# SCH_-_USB_Passthrough_v2_0.net
KiCad netlist of a schematic drawn in EasyEDA
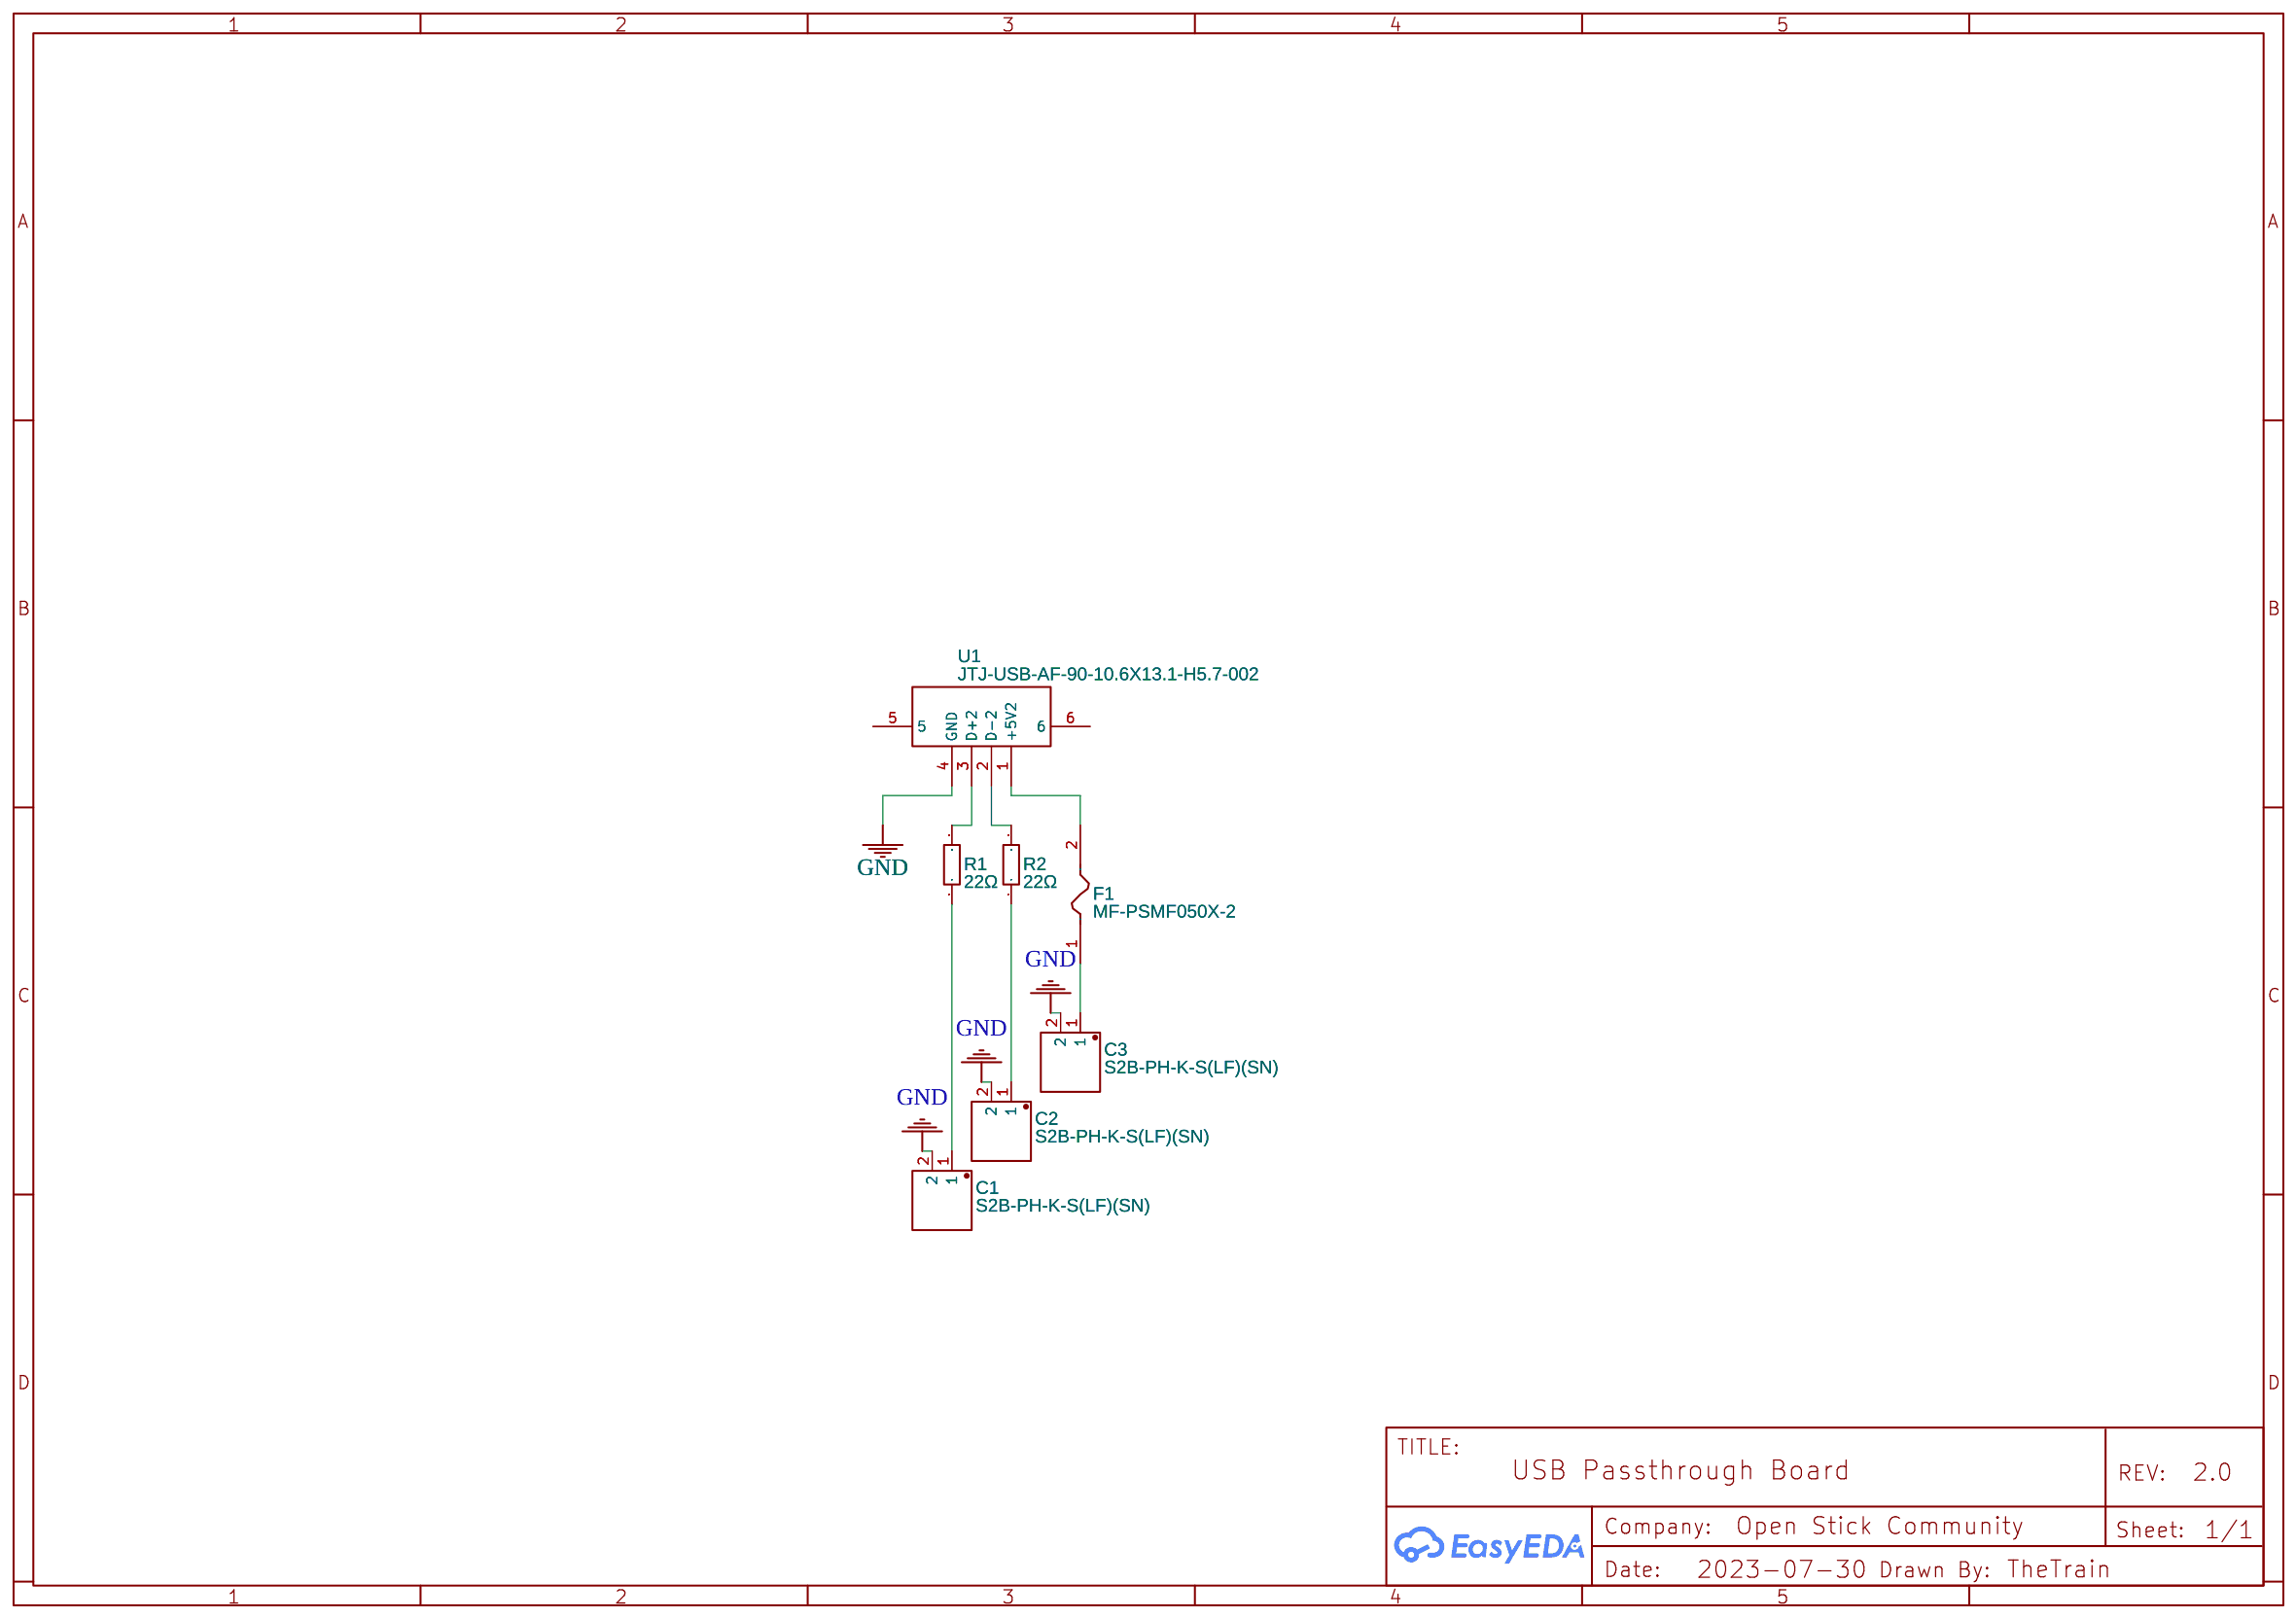
[diagram p0: schematic sheet]

(export (version "E")
  (design (tool "Eeschema 10.0.6"))
  (components
    (comp (ref "C1")
      (value "S2B-PH-K-S(LF)(SN)")
      (fields (field (name "Manufacturer") "JST"))
      (libsource (lib "") (part "S2B-PH-K-S(LF)(SN)"))
    )
    (comp (ref "C2")
      (value "S2B-PH-K-S(LF)(SN)")
      (fields (field (name "Manufacturer") "JST"))
      (libsource (lib "") (part "S2B-PH-K-S(LF)(SN)"))
    )
    (comp (ref "C3")
      (value "S2B-PH-K-S(LF)(SN)")
      (fields (field (name "Manufacturer") "JST"))
      (libsource (lib "") (part "S2B-PH-K-S(LF)(SN)"))
    )
    (comp (ref "F1")
      (value "MF-PSMF050X-2")
      (fields (field (name "Manufacturer") "BOURNS"))
      (libsource (lib "") (part "MF-PSMF050X-2"))
    )
    (comp (ref "R1")
      (value "22Ω")
      (fields
        (field (name "Manufacturer Part") "0603WAF220JT5E")
        (field (name "Manufacturer") "UNI-ROYAL(厚声)")
      )
      (libsource (lib "") (part "0603WAF220JT5E"))
    )
    (comp (ref "R2")
      (value "22Ω")
      (fields
        (field (name "Manufacturer Part") "0603WAF220JT5E")
        (field (name "Manufacturer") "UNI-ROYAL(厚声)")
      )
      (libsource (lib "") (part "0603WAF220JT5E"))
    )
    (comp (ref "U1")
      (value "JTJ-USB-AF-90-10.6X13.1-H5.7-002")
      (fields (field (name "Manufacturer Part") "912-121A2026S10100") (field (name "Manufacturer") "精拓金"))
      (libsource (lib "") (part "JTJ-USB-AF-90-10.6X13.1-H5.7-002"))
    )
  )
  (nets
    (net (code "1") (name "GND") (class "Default")
      (node (ref "C1") (pin "2") (pinfunction "2_2") (pintype "unspecified"))
      (node (ref "C2") (pin "2") (pinfunction "2_2") (pintype "unspecified"))
      (node (ref "C3") (pin "2") (pinfunction "2_2") (pintype "unspecified"))
      (node (ref "U1") (pin "4") (pinfunction "GND_4") (pintype "unspecified"))
    )
    (net (code "2") (name "Net-(C1-Pad1)") (class "Default")
      (node (ref "C1") (pin "1") (pinfunction "1_1") (pintype "unspecified"))
      (node (ref "R1") (pin "1") (pinfunction "1_1") (pintype "input"))
    )
    (net (code "3") (name "Net-(C2-Pad1)") (class "Default")
      (node (ref "C2") (pin "1") (pinfunction "1_1") (pintype "unspecified"))
      (node (ref "R2") (pin "1") (pinfunction "1_1") (pintype "input"))
    )
    (net (code "4") (name "Net-(C3-Pad1)") (class "Default")
      (node (ref "C3") (pin "1") (pinfunction "1_1") (pintype "unspecified"))
      (node (ref "F1") (pin "1") (pinfunction "1_1") (pintype "unspecified"))
    )
    (net (code "5") (name "Net-(U1-+5V2)") (class "Default")
      (node (ref "F1") (pin "2") (pinfunction "2_2") (pintype "unspecified"))
      (node (ref "U1") (pin "1") (pinfunction "+5V2_1") (pintype "unspecified"))
    )
    (net (code "6") (name "Net-(U1-D+2)") (class "Default")
      (node (ref "R1") (pin "2") (pinfunction "2_2") (pintype "input"))
      (node (ref "U1") (pin "3") (pinfunction "D+2_3") (pintype "unspecified"))
    )
    (net (code "7") (name "Net-(U1-D-2)") (class "Default")
      (node (ref "R2") (pin "2") (pinfunction "2_2") (pintype "input"))
      (node (ref "U1") (pin "2") (pinfunction "D-2_2") (pintype "unspecified"))
    )
    (net (code "8") (name "unconnected-(U1-Pad5)") (class "Default")
      (node (ref "U1") (pin "5") (pinfunction "5_5") (pintype "unspecified"))
    )
    (net (code "9") (name "unconnected-(U1-Pad6)") (class "Default")
      (node (ref "U1") (pin "6") (pinfunction "6_6") (pintype "unspecified"))
    )
  )
)
